# RobotDriverSCH.net
KiCad netlist of a schematic drawn in Altium Designer
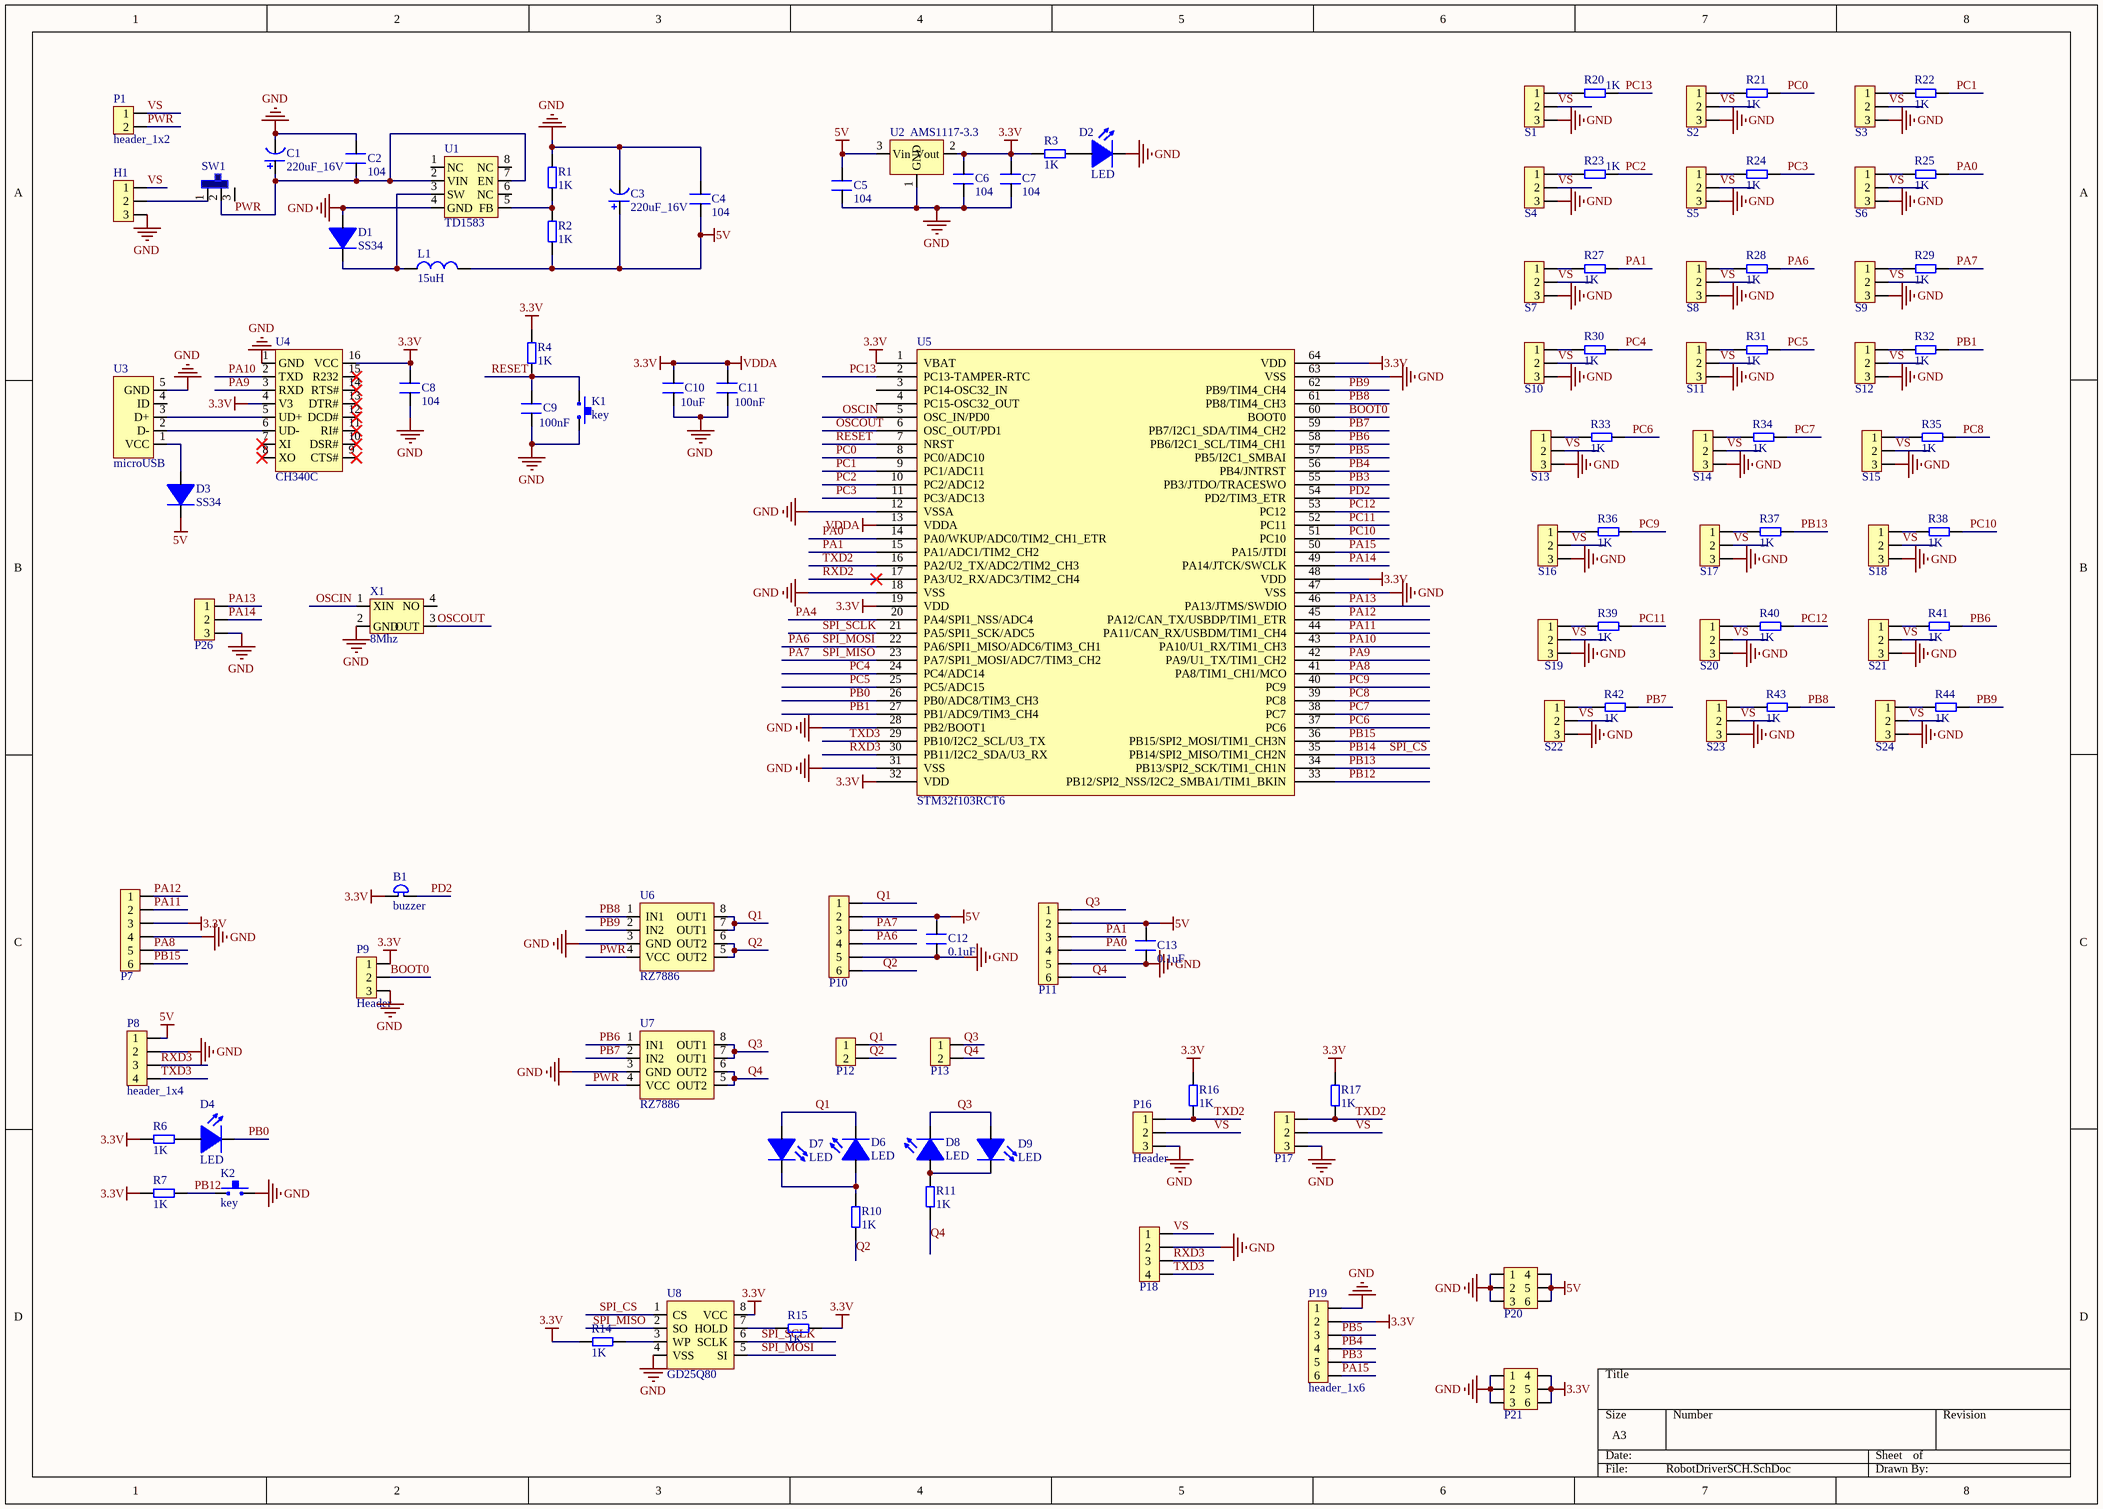
[diagram p0: RobotDriverSCH.SchDoc]

(export (version "E")
  (design (tool "Eeschema 10.0.6"))
  (components
    (comp (ref "B1")
      (value "buzzer")
      (footprint "BEEP 5x9x5.5")
      (libsource (lib "RobotDriverSCHLib") (part "buzzer"))
    )
    (comp (ref "C1")
      (value "220uF_16V")
      (footprint "CM D(6.3*7.7)")
      (libsource (lib "RobotDriverSCHLib") (part "CAP_220uF_16V"))
    )
    (comp (ref "C2") (value "104") (footprint "C 0603") (libsource (lib "RobotDriverSCHLib") (part "C_0603")))
    (comp (ref "C3")
      (value "220uF_16V")
      (footprint "CM D(6.3*7.7)")
      (libsource (lib "RobotDriverSCHLib") (part "CAP_220uF_16V"))
    )
    (comp (ref "C4") (value "104") (footprint "C 0603") (libsource (lib "RobotDriverSCHLib") (part "C_0603")))
    (comp (ref "C5") (value "104") (footprint "C 0603") (libsource (lib "RobotDriverSCHLib") (part "C_0603")))
    (comp (ref "C6") (value "104") (footprint "C 0603") (libsource (lib "RobotDriverSCHLib") (part "C_0603")))
    (comp (ref "C7") (value "104") (footprint "C 0603") (libsource (lib "RobotDriverSCHLib") (part "C_0603")))
    (comp (ref "C8") (value "104") (footprint "C 0603") (libsource (lib "RobotDriverSCHLib") (part "C_0603")))
    (comp (ref "C9")
      (value "100nF")
      (footprint "C 0603")
      (libsource (lib "RobotDriverSCHLib") (part "C_0603"))
    )
    (comp (ref "C10")
      (value "10uF")
      (footprint "C 0603")
      (libsource (lib "RobotDriverSCHLib") (part "C_0603"))
    )
    (comp (ref "C11")
      (value "100nF")
      (footprint "C 0603")
      (libsource (lib "RobotDriverSCHLib") (part "C_0603"))
    )
    (comp (ref "C12")
      (value "0.1uF")
      (footprint "C 0603")
      (libsource (lib "RobotDriverSCHLib") (part "C_0603"))
    )
    (comp (ref "C13")
      (value "0.1uF")
      (footprint "C 0603")
      (libsource (lib "RobotDriverSCHLib") (part "C_0603"))
    )
    (comp (ref "D1") (value "SS34") (footprint "SMA") (libsource (lib "RobotDriverSCHLib") (part "SS34")))
    (comp (ref "D2") (value "LED") (footprint "LED 0603R") (libsource (lib "RobotDriverSCHLib") (part "LED")))
    (comp (ref "D3") (value "SS34") (footprint "SMA") (libsource (lib "RobotDriverSCHLib") (part "SS34")))
    (comp (ref "D4") (value "LED") (footprint "LED 0603R") (libsource (lib "RobotDriverSCHLib") (part "LED")))
    (comp (ref "D6") (value "LED") (footprint "LED 0603R") (libsource (lib "RobotDriverSCHLib") (part "LED")))
    (comp (ref "D7") (value "LED") (footprint "LED 0603R") (libsource (lib "RobotDriverSCHLib") (part "LED")))
    (comp (ref "D8") (value "LED") (footprint "LED 0603R") (libsource (lib "RobotDriverSCHLib") (part "LED")))
    (comp (ref "D9") (value "LED") (footprint "LED 0603R") (libsource (lib "RobotDriverSCHLib") (part "LED")))
    (comp (ref "H1")
      (value "header")
      (footprint "KF128-3.81-3P")
      (libsource (lib "RobotDriverSCHLib") (part "PowerHead"))
    )
    (comp (ref "K1") (value "key") (footprint "TSW SMD-3*6*4.3") (libsource (lib "") (part "key_1")))
    (comp (ref "K2")
      (value "key")
      (footprint "TSW SMD-3*6*4.3")
      (libsource (lib "RobotDriverSCHLib") (part "key"))
    )
    (comp (ref "L1")
      (value "15uH")
      (footprint "NR6045")
      (libsource (lib "RobotDriverSCHLib") (part "L_6045"))
    )
    (comp (ref "P1")
      (value "header_1x2")
      (footprint "HDR2.54-LI-2P")
      (libsource (lib "RobotDriverSCHLib") (part "header_1x2"))
    )
    (comp (ref "P7")
      (value "PS2无线手柄")
      (footprint "XH2.54-LI-6P")
      (libsource (lib "RobotDriverSCHLib") (part "xh2.54_1x6"))
    )
    (comp (ref "P8")
      (value "header_1x4")
      (footprint "HDR2.54-LI-4P")
      (libsource (lib "RobotDriverSCHLib") (part "header_1x4"))
    )
    (comp (ref "P9")
      (value "Header")
      (footprint "HDR2.54-LI-3P")
      (libsource (lib "RobotDriverSCHLib") (part "header_1x3"))
    )
    (comp (ref "P10")
      (value "XH2.54W_1X6")
      (footprint "XH2.54-WI-6P")
      (libsource (lib "RobotDriverSCHLib") (part "XH2.54W_1X6"))
    )
    (comp (ref "P11")
      (value "XH2.54W_1X6")
      (footprint "XH2.54-WI-6P")
      (libsource (lib "RobotDriverSCHLib") (part "XH2.54W_1X6"))
    )
    (comp (ref "P12")
      (value "KF2.54_1x2")
      (footprint "KF2EDGK-2.54-WI-2P")
      (libsource (lib "RobotDriverSCHLib") (part "KF2.54_1x2"))
    )
    (comp (ref "P13")
      (value "KF2.54_1x2")
      (footprint "KF2EDGK-2.54-WI-2P")
      (libsource (lib "RobotDriverSCHLib") (part "KF2.54_1x2"))
    )
    (comp (ref "P16")
      (value "Header")
      (footprint "XH2.54-WI-3P")
      (libsource (lib "RobotDriverSCHLib") (part "header_1x3"))
    )
    (comp (ref "P17")
      (value "Header")
      (footprint "XH2.54-WI-3P")
      (libsource (lib "RobotDriverSCHLib") (part "header_1x3"))
    )
    (comp (ref "P18")
      (value "header_1x4")
      (footprint "XH2.54-WI-4P")
      (libsource (lib "RobotDriverSCHLib") (part "header_1x4"))
    )
    (comp (ref "P19")
      (value "header_1x6")
      (footprint "HDR2.54-M-LI-6P")
      (libsource (lib "RobotDriverSCHLib") (part "header_1x6"))
    )
    (comp (ref "P20")
      (value "Header2x3")
      (footprint "HDR2.54-LI-2x3P")
      (libsource (lib "RobotDriverSCHLib") (part "Header2x3"))
    )
    (comp (ref "P21")
      (value "Header2x3")
      (footprint "HDR2.54-LI-2x3P")
      (libsource (lib "RobotDriverSCHLib") (part "Header2x3"))
    )
    (comp (ref "P26")
      (value "Head_1x3")
      (footprint "HDR2.54-LI-3P")
      (libsource (lib "RobotDriverSCHLib") (part "Head_1x3"))
    )
    (comp (ref "R1") (value "1K") (footprint "0603R") (libsource (lib "RobotDriverSCHLib") (part "R_0603")))
    (comp (ref "R2") (value "1K") (footprint "0603R") (libsource (lib "RobotDriverSCHLib") (part "R_0603")))
    (comp (ref "R3") (value "1K") (footprint "0603R") (libsource (lib "RobotDriverSCHLib") (part "R_0603")))
    (comp (ref "R4") (value "1K") (footprint "0603R") (libsource (lib "RobotDriverSCHLib") (part "R_0603")))
    (comp (ref "R6") (value "1K") (footprint "0603R") (libsource (lib "RobotDriverSCHLib") (part "R_0603")))
    (comp (ref "R7") (value "1K") (footprint "0603R") (libsource (lib "RobotDriverSCHLib") (part "R_0603")))
    (comp (ref "R10") (value "1K") (footprint "0603R") (libsource (lib "RobotDriverSCHLib") (part "R_0603")))
    (comp (ref "R11") (value "1K") (footprint "0603R") (libsource (lib "RobotDriverSCHLib") (part "R_0603")))
    (comp (ref "R14") (value "1K") (footprint "0603R") (libsource (lib "RobotDriverSCHLib") (part "R_0603")))
    (comp (ref "R15") (value "1K") (footprint "0603R") (libsource (lib "RobotDriverSCHLib") (part "R_0603")))
    (comp (ref "R16") (value "1K") (footprint "0603R") (libsource (lib "RobotDriverSCHLib") (part "R_0603")))
    (comp (ref "R17") (value "1K") (footprint "0603R") (libsource (lib "RobotDriverSCHLib") (part "R_0603")))
    (comp (ref "R20") (value "1K") (footprint "0603R") (libsource (lib "RobotDriverSCHLib") (part "R_0603")))
    (comp (ref "R21") (value "1K") (footprint "0603R") (libsource (lib "RobotDriverSCHLib") (part "R_0603")))
    (comp (ref "R22") (value "1K") (footprint "0603R") (libsource (lib "RobotDriverSCHLib") (part "R_0603")))
    (comp (ref "R23") (value "1K") (footprint "0603R") (libsource (lib "RobotDriverSCHLib") (part "R_0603")))
    (comp (ref "R24") (value "1K") (footprint "0603R") (libsource (lib "RobotDriverSCHLib") (part "R_0603")))
    (comp (ref "R25") (value "1K") (footprint "0603R") (libsource (lib "RobotDriverSCHLib") (part "R_0603")))
    (comp (ref "R27") (value "1K") (footprint "0603R") (libsource (lib "RobotDriverSCHLib") (part "R_0603")))
    (comp (ref "R28") (value "1K") (footprint "0603R") (libsource (lib "RobotDriverSCHLib") (part "R_0603")))
    (comp (ref "R29") (value "1K") (footprint "0603R") (libsource (lib "RobotDriverSCHLib") (part "R_0603")))
    (comp (ref "R30") (value "1K") (footprint "0603R") (libsource (lib "RobotDriverSCHLib") (part "R_0603")))
    (comp (ref "R31") (value "1K") (footprint "0603R") (libsource (lib "RobotDriverSCHLib") (part "R_0603")))
    (comp (ref "R32") (value "1K") (footprint "0603R") (libsource (lib "RobotDriverSCHLib") (part "R_0603")))
    (comp (ref "R33") (value "1K") (footprint "0603R") (libsource (lib "RobotDriverSCHLib") (part "R_0603")))
    (comp (ref "R34") (value "1K") (footprint "0603R") (libsource (lib "RobotDriverSCHLib") (part "R_0603")))
    (comp (ref "R35") (value "1K") (footprint "0603R") (libsource (lib "RobotDriverSCHLib") (part "R_0603")))
    (comp (ref "R36") (value "1K") (footprint "0603R") (libsource (lib "RobotDriverSCHLib") (part "R_0603")))
    (comp (ref "R37") (value "1K") (footprint "0603R") (libsource (lib "RobotDriverSCHLib") (part "R_0603")))
    (comp (ref "R38") (value "1K") (footprint "0603R") (libsource (lib "RobotDriverSCHLib") (part "R_0603")))
    (comp (ref "R39") (value "1K") (footprint "0603R") (libsource (lib "RobotDriverSCHLib") (part "R_0603")))
    (comp (ref "R40") (value "1K") (footprint "0603R") (libsource (lib "RobotDriverSCHLib") (part "R_0603")))
    (comp (ref "R41") (value "1K") (footprint "0603R") (libsource (lib "RobotDriverSCHLib") (part "R_0603")))
    (comp (ref "R42") (value "1K") (footprint "0603R") (libsource (lib "RobotDriverSCHLib") (part "R_0603")))
    (comp (ref "R43") (value "1K") (footprint "0603R") (libsource (lib "RobotDriverSCHLib") (part "R_0603")))
    (comp (ref "R44") (value "1K") (footprint "0603R") (libsource (lib "RobotDriverSCHLib") (part "R_0603")))
    (comp (ref "S1")
      (value "Header")
      (footprint "HDR2.54-LI-3P")
      (libsource (lib "RobotDriverSCHLib") (part "header_1x3"))
    )
    (comp (ref "S2")
      (value "Header")
      (footprint "HDR2.54-LI-3P")
      (libsource (lib "RobotDriverSCHLib") (part "header_1x3"))
    )
    (comp (ref "S3")
      (value "Header")
      (footprint "HDR2.54-LI-3P")
      (libsource (lib "RobotDriverSCHLib") (part "header_1x3"))
    )
    (comp (ref "S4")
      (value "Header")
      (footprint "HDR2.54-LI-3P")
      (libsource (lib "RobotDriverSCHLib") (part "header_1x3"))
    )
    (comp (ref "S5")
      (value "Header")
      (footprint "HDR2.54-LI-3P")
      (libsource (lib "RobotDriverSCHLib") (part "header_1x3"))
    )
    (comp (ref "S6")
      (value "Header")
      (footprint "HDR2.54-LI-3P")
      (libsource (lib "RobotDriverSCHLib") (part "header_1x3"))
    )
    (comp (ref "S7")
      (value "Header")
      (footprint "HDR2.54-LI-3P")
      (libsource (lib "RobotDriverSCHLib") (part "header_1x3"))
    )
    (comp (ref "S8")
      (value "Header")
      (footprint "HDR2.54-LI-3P")
      (libsource (lib "RobotDriverSCHLib") (part "header_1x3"))
    )
    (comp (ref "S9")
      (value "Header")
      (footprint "HDR2.54-LI-3P")
      (libsource (lib "RobotDriverSCHLib") (part "header_1x3"))
    )
    (comp (ref "S10")
      (value "Header")
      (footprint "HDR2.54-LI-3P")
      (libsource (lib "RobotDriverSCHLib") (part "header_1x3"))
    )
    (comp (ref "S11")
      (value "Header")
      (footprint "HDR2.54-LI-3P")
      (libsource (lib "RobotDriverSCHLib") (part "header_1x3"))
    )
    (comp (ref "S12")
      (value "Header")
      (footprint "HDR2.54-LI-3P")
      (libsource (lib "RobotDriverSCHLib") (part "header_1x3"))
    )
    (comp (ref "S13")
      (value "Header")
      (footprint "HDR2.54-LI-3P")
      (libsource (lib "RobotDriverSCHLib") (part "header_1x3"))
    )
    (comp (ref "S14")
      (value "Header")
      (footprint "HDR2.54-LI-3P")
      (libsource (lib "RobotDriverSCHLib") (part "header_1x3"))
    )
    (comp (ref "S15")
      (value "Header")
      (footprint "HDR2.54-LI-3P")
      (libsource (lib "RobotDriverSCHLib") (part "header_1x3"))
    )
    (comp (ref "S16")
      (value "Header")
      (footprint "HDR2.54-LI-3P")
      (libsource (lib "RobotDriverSCHLib") (part "header_1x3"))
    )
    (comp (ref "S17")
      (value "Header")
      (footprint "HDR2.54-LI-3P")
      (libsource (lib "RobotDriverSCHLib") (part "header_1x3"))
    )
    (comp (ref "S18")
      (value "Header")
      (footprint "HDR2.54-LI-3P")
      (libsource (lib "RobotDriverSCHLib") (part "header_1x3"))
    )
    (comp (ref "S19")
      (value "Header")
      (footprint "HDR2.54-LI-3P")
      (libsource (lib "RobotDriverSCHLib") (part "header_1x3"))
    )
    (comp (ref "S20")
      (value "Header")
      (footprint "HDR2.54-LI-3P")
      (libsource (lib "RobotDriverSCHLib") (part "header_1x3"))
    )
    (comp (ref "S21")
      (value "Header")
      (footprint "HDR2.54-LI-3P")
      (libsource (lib "RobotDriverSCHLib") (part "header_1x3"))
    )
    (comp (ref "S22")
      (value "Header")
      (footprint "HDR2.54-LI-3P")
      (libsource (lib "RobotDriverSCHLib") (part "header_1x3"))
    )
    (comp (ref "S23")
      (value "Header")
      (footprint "HDR2.54-LI-3P")
      (libsource (lib "RobotDriverSCHLib") (part "header_1x3"))
    )
    (comp (ref "S24")
      (value "Header")
      (footprint "HDR2.54-LI-3P")
      (libsource (lib "RobotDriverSCHLib") (part "header_1x3"))
    )
    (comp (ref "SW1")
      (value "Switch")
      (footprint "SS12D10")
      (libsource (lib "RobotDriverSCHLib") (part "SS12D10"))
    )
    (comp (ref "U1")
      (value "TD1583")
      (footprint "SOP8")
      (libsource (lib "RobotDriverSCHLib") (part "TD1583"))
    )
    (comp (ref "U2")
      (value "AMS1117-3.3")
      (footprint "SOT-223")
      (libsource (lib "RobotDriverSCHLib") (part "AMS1117-3.3"))
    )
    (comp (ref "U3")
      (value "microUSB")
      (footprint "USB-MICRO_B")
      (libsource (lib "RobotDriverSCHLib") (part "MicroUSB_B"))
    )
    (comp (ref "U4")
      (value "CH340C")
      (footprint "SOP16")
      (libsource (lib "RobotDriverSCHLib") (part "CH340C"))
    )
    (comp (ref "U5")
      (value "STM32f103RCT6")
      (footprint "LQFP_64")
      (libsource (lib "RobotDriverSCHLib") (part "STM32f103RCT6"))
    )
    (comp (ref "U6")
      (value "RZ7886")
      (footprint "DIP8")
      (libsource (lib "RobotDriverSCHLib") (part "RZ7886"))
    )
    (comp (ref "U7")
      (value "RZ7886")
      (footprint "DIP8")
      (libsource (lib "RobotDriverSCHLib") (part "RZ7886"))
    )
    (comp (ref "U8")
      (value "GD25Q80")
      (footprint "SOP8")
      (libsource (lib "RobotDriverSCHLib") (part "flash"))
    )
    (comp (ref "X1")
      (value "8Mhz")
      (footprint "OSC 3225-4P")
      (libsource (lib "RobotDriverSCHLib") (part "XTAL"))
    )
  )
  (nets
    (net (code "1") (name "/BOOT0") (class "Default")
      (node (ref "P9") (pin "2") (pinfunction "2_2") (pintype "passive"))
      (node (ref "U5") (pin "60") (pinfunction "BOOT0_60") (pintype "passive"))
    )
    (net (code "2") (name "/OSCIN") (class "Default")
      (node (ref "U5") (pin "5") (pinfunction "OSC_IN/PD0_5") (pintype "passive"))
      (node (ref "X1") (pin "1") (pinfunction "XIN_1") (pintype "passive"))
    )
    (net (code "3") (name "/OSCOUT") (class "Default")
      (node (ref "U5") (pin "6") (pinfunction "OSC_OUT/PD1_6") (pintype "passive"))
      (node (ref "X1") (pin "3") (pinfunction "OUT_3") (pintype "passive"))
    )
    (net (code "4") (name "/PA0") (class "Default")
      (node (ref "P11") (pin "4") (pinfunction "4_4") (pintype "passive"))
      (node (ref "R25") (pin "2") (pinfunction "2_2") (pintype "passive"))
      (node (ref "U5") (pin "14") (pinfunction "PA0/WKUP/ADC0/TIM2_CH1_ETR_14") (pintype "passive"))
    )
    (net (code "5") (name "/PA1") (class "Default")
      (node (ref "P11") (pin "3") (pinfunction "3_3") (pintype "passive"))
      (node (ref "R27") (pin "2") (pinfunction "2_2") (pintype "passive"))
      (node (ref "U5") (pin "15") (pinfunction "PA1/ADC1/TIM2_CH2_15") (pintype "passive"))
    )
    (net (code "6") (name "/PA4") (class "Default")
      (node (ref "U5") (pin "20") (pinfunction "PA4/SPI1_NSS/ADC4_20") (pintype "passive"))
    )
    (net (code "7") (name "/PA6") (class "Default")
      (node (ref "P10") (pin "4") (pinfunction "4_4") (pintype "passive"))
      (node (ref "R28") (pin "2") (pinfunction "2_2") (pintype "passive"))
      (node (ref "U5") (pin "22") (pinfunction "PA6/SPI1_MISO/ADC6/TIM3_CH1_22") (pintype "passive"))
      (node (ref "U8") (pin "5") (pinfunction "SI_5") (pintype "passive"))
    )
    (net (code "8") (name "/PA7") (class "Default")
      (node (ref "P10") (pin "3") (pinfunction "3_3") (pintype "passive"))
      (node (ref "R29") (pin "2") (pinfunction "2_2") (pintype "passive"))
      (node (ref "U5") (pin "23") (pinfunction "PA7/SPI1_MOSI/ADC7/TIM3_CH2_23") (pintype "passive"))
      (node (ref "U8") (pin "2") (pinfunction "SO_2") (pintype "passive"))
    )
    (net (code "9") (name "/PA8") (class "Default")
      (node (ref "P7") (pin "5") (pinfunction "5_5") (pintype "passive"))
      (node (ref "U5") (pin "41") (pinfunction "PA8/TIM1_CH1/MCO_41") (pintype "passive"))
    )
    (net (code "10") (name "/PA9") (class "Default")
      (node (ref "U4") (pin "3") (pinfunction "RXD_3") (pintype "passive"))
      (node (ref "U5") (pin "42") (pinfunction "PA9/U1_TX/TIM1_CH2_42") (pintype "passive"))
    )
    (net (code "11") (name "/PA10") (class "Default")
      (node (ref "U4") (pin "2") (pinfunction "TXD_2") (pintype "passive"))
      (node (ref "U5") (pin "43") (pinfunction "PA10/U1_RX/TIM1_CH3_43") (pintype "passive"))
    )
    (net (code "12") (name "/PA11") (class "Default")
      (node (ref "P7") (pin "2") (pinfunction "2_2") (pintype "passive"))
      (node (ref "U5") (pin "44") (pinfunction "PA11/CAN_RX/USBDM/TIM1_CH4_44") (pintype "passive"))
    )
    (net (code "13") (name "/PA12") (class "Default")
      (node (ref "P7") (pin "1") (pinfunction "1_1") (pintype "passive"))
      (node (ref "U5") (pin "45") (pinfunction "PA12/CAN_TX/USBDP/TIM1_ETR_45") (pintype "passive"))
    )
    (net (code "14") (name "/PA13") (class "Default")
      (node (ref "P26") (pin "1") (pinfunction "1_1") (pintype "passive"))
      (node (ref "U5") (pin "46") (pinfunction "PA13/JTMS/SWDIO_46") (pintype "passive"))
    )
    (net (code "15") (name "/PA14") (class "Default")
      (node (ref "P26") (pin "2") (pinfunction "2_2") (pintype "passive"))
      (node (ref "U5") (pin "49") (pinfunction "PA14/JTCK/SWCLK_49") (pintype "passive"))
    )
    (net (code "16") (name "/PA15") (class "Default")
      (node (ref "P19") (pin "6") (pinfunction "6_6") (pintype "passive"))
      (node (ref "U5") (pin "50") (pinfunction "PA15/JTDI_50") (pintype "passive"))
    )
    (net (code "17") (name "/PB0") (class "Default")
      (node (ref "D4") (pin "2") (pinfunction "2_2") (pintype "passive"))
      (node (ref "U5") (pin "26") (pinfunction "PB0/ADC8/TIM3_CH3_26") (pintype "passive"))
    )
    (net (code "18") (name "/PB1") (class "Default")
      (node (ref "R32") (pin "2") (pinfunction "2_2") (pintype "passive"))
      (node (ref "U5") (pin "27") (pinfunction "PB1/ADC9/TIM3_CH4_27") (pintype "passive"))
    )
    (net (code "19") (name "/PB3") (class "Default")
      (node (ref "P19") (pin "5") (pinfunction "5_5") (pintype "passive"))
      (node (ref "U5") (pin "55") (pinfunction "PB3/JTDO/TRACESWO_55") (pintype "passive"))
    )
    (net (code "20") (name "/PB4") (class "Default")
      (node (ref "P19") (pin "4") (pinfunction "4_4") (pintype "passive"))
      (node (ref "U5") (pin "56") (pinfunction "PB4/JNTRST_56") (pintype "passive"))
    )
    (net (code "21") (name "/PB5") (class "Default")
      (node (ref "P19") (pin "3") (pinfunction "3_3") (pintype "passive"))
      (node (ref "U5") (pin "57") (pinfunction "PB5/I2C1_SMBAI_57") (pintype "passive"))
    )
    (net (code "22") (name "/PB6") (class "Default")
      (node (ref "R41") (pin "2") (pinfunction "2_2") (pintype "passive"))
      (node (ref "U5") (pin "58") (pinfunction "PB6/I2C1_SCL/TIM4_CH1_58") (pintype "passive"))
      (node (ref "U7") (pin "1") (pinfunction "IN1_1") (pintype "passive"))
    )
    (net (code "23") (name "/PB7") (class "Default")
      (node (ref "R42") (pin "2") (pinfunction "2_2") (pintype "passive"))
      (node (ref "U5") (pin "59") (pinfunction "PB7/I2C1_SDA/TIM4_CH2_59") (pintype "passive"))
      (node (ref "U7") (pin "2") (pinfunction "IN2_2") (pintype "passive"))
    )
    (net (code "24") (name "/PB8") (class "Default")
      (node (ref "R43") (pin "2") (pinfunction "2_2") (pintype "passive"))
      (node (ref "U5") (pin "61") (pinfunction "PB8/TIM4_CH3_61") (pintype "passive"))
      (node (ref "U6") (pin "1") (pinfunction "IN1_1") (pintype "passive"))
    )
    (net (code "25") (name "/PB9") (class "Default")
      (node (ref "R44") (pin "2") (pinfunction "2_2") (pintype "passive"))
      (node (ref "U5") (pin "62") (pinfunction "PB9/TIM4_CH4_62") (pintype "passive"))
      (node (ref "U6") (pin "2") (pinfunction "IN2_2") (pintype "passive"))
    )
    (net (code "26") (name "/PB12") (class "Default")
      (node (ref "K2") (pin "1") (pinfunction "1_1") (pintype "passive"))
      (node (ref "R7") (pin "2") (pinfunction "2_2") (pintype "passive"))
      (node (ref "U5") (pin "33") (pinfunction "PB12/SPI2_NSS/I2C2_SMBA1/TIM1_BKIN_33") (pintype "passive"))
    )
    (net (code "27") (name "/PB13") (class "Default")
      (node (ref "R37") (pin "2") (pinfunction "2_2") (pintype "passive"))
      (node (ref "U5") (pin "34") (pinfunction "PB13/SPI2_SCK/TIM1_CH1N_34") (pintype "passive"))
    )
    (net (code "28") (name "/PB14") (class "Default")
      (node (ref "U5") (pin "35") (pinfunction "PB14/SPI2_MISO/TIM1_CH2N_35") (pintype "passive"))
      (node (ref "U8") (pin "1") (pinfunction "CS_1") (pintype "passive"))
    )
    (net (code "29") (name "/PB15") (class "Default")
      (node (ref "P7") (pin "6") (pinfunction "6_6") (pintype "passive"))
      (node (ref "U5") (pin "36") (pinfunction "PB15/SPI2_MOSI/TIM1_CH3N_36") (pintype "passive"))
    )
    (net (code "30") (name "/PC0") (class "Default")
      (node (ref "R21") (pin "2") (pinfunction "2_2") (pintype "passive"))
      (node (ref "U5") (pin "8") (pinfunction "PC0/ADC10_8") (pintype "passive"))
    )
    (net (code "31") (name "/PC1") (class "Default")
      (node (ref "R22") (pin "2") (pinfunction "2_2") (pintype "passive"))
      (node (ref "U5") (pin "9") (pinfunction "PC1/ADC11_9") (pintype "passive"))
    )
    (net (code "32") (name "/PC2") (class "Default")
      (node (ref "R23") (pin "2") (pinfunction "2_2") (pintype "passive"))
      (node (ref "U5") (pin "10") (pinfunction "PC2/ADC12_10") (pintype "passive"))
    )
    (net (code "33") (name "/PC3") (class "Default")
      (node (ref "R24") (pin "2") (pinfunction "2_2") (pintype "passive"))
      (node (ref "U5") (pin "11") (pinfunction "PC3/ADC13_11") (pintype "passive"))
    )
    (net (code "34") (name "/PC4") (class "Default")
      (node (ref "R30") (pin "2") (pinfunction "2_2") (pintype "passive"))
      (node (ref "U5") (pin "24") (pinfunction "PC4/ADC14_24") (pintype "passive"))
    )
    (net (code "35") (name "/PC5") (class "Default")
      (node (ref "R31") (pin "2") (pinfunction "2_2") (pintype "passive"))
      (node (ref "U5") (pin "25") (pinfunction "PC5/ADC15_25") (pintype "passive"))
    )
    (net (code "36") (name "/PC6") (class "Default")
      (node (ref "R33") (pin "2") (pinfunction "2_2") (pintype "passive"))
      (node (ref "U5") (pin "37") (pinfunction "PC6_37") (pintype "passive"))
    )
    (net (code "37") (name "/PC7") (class "Default")
      (node (ref "R34") (pin "2") (pinfunction "2_2") (pintype "passive"))
      (node (ref "U5") (pin "38") (pinfunction "PC7_38") (pintype "passive"))
    )
    (net (code "38") (name "/PC8") (class "Default")
      (node (ref "R35") (pin "2") (pinfunction "2_2") (pintype "passive"))
      (node (ref "U5") (pin "39") (pinfunction "PC8_39") (pintype "passive"))
    )
    (net (code "39") (name "/PC9") (class "Default")
      (node (ref "R36") (pin "2") (pinfunction "2_2") (pintype "passive"))
      (node (ref "U5") (pin "40") (pinfunction "PC9_40") (pintype "passive"))
    )
    (net (code "40") (name "/PC10") (class "Default")
      (node (ref "R38") (pin "2") (pinfunction "2_2") (pintype "passive"))
      (node (ref "U5") (pin "51") (pinfunction "PC10_51") (pintype "passive"))
    )
    (net (code "41") (name "/PC11") (class "Default")
      (node (ref "R39") (pin "2") (pinfunction "2_2") (pintype "passive"))
      (node (ref "U5") (pin "52") (pinfunction "PC11_52") (pintype "passive"))
    )
    (net (code "42") (name "/PC12") (class "Default")
      (node (ref "R40") (pin "2") (pinfunction "2_2") (pintype "passive"))
      (node (ref "U5") (pin "53") (pinfunction "PC12_53") (pintype "passive"))
    )
    (net (code "43") (name "/PC13") (class "Default")
      (node (ref "R20") (pin "2") (pinfunction "2_2") (pintype "passive"))
      (node (ref "U5") (pin "2") (pinfunction "PC13-TAMPER-RTC_2") (pintype "passive"))
    )
    (net (code "44") (name "/PD2") (class "Default")
      (node (ref "B1") (pin "2") (pinfunction "2_2") (pintype "passive"))
      (node (ref "U5") (pin "54") (pinfunction "PD2/TIM3_ETR_54") (pintype "passive"))
    )
    (net (code "45") (name "/PWR") (class "Default")
      (node (ref "C1") (pin "1") (pinfunction "1_1") (pintype "passive"))
      (node (ref "C2") (pin "2") (pinfunction "2_2") (pintype "passive"))
      (node (ref "P1") (pin "2") (pinfunction "2_2") (pintype "passive"))
      (node (ref "SW1") (pin "2") (pinfunction "2_2") (pintype "passive"))
      (node (ref "U1") (pin "2") (pinfunction "VIN_2") (pintype "passive"))
      (node (ref "U1") (pin "7") (pinfunction "EN_7") (pintype "passive"))
      (node (ref "U6") (pin "4") (pinfunction "VCC_4") (pintype "passive"))
      (node (ref "U7") (pin "4") (pinfunction "VCC_4") (pintype "passive"))
    )
    (net (code "46") (name "/Q1") (class "Default")
      (node (ref "D6") (pin "2") (pinfunction "2_2") (pintype "passive"))
      (node (ref "D7") (pin "1") (pinfunction "1_1") (pintype "passive"))
      (node (ref "P10") (pin "1") (pinfunction "1_1") (pintype "passive"))
      (node (ref "P12") (pin "1") (pinfunction "1_1") (pintype "passive"))
      (node (ref "U6") (pin "7") (pinfunction "OUT1_7") (pintype "passive"))
      (node (ref "U6") (pin "8") (pinfunction "OUT1_8") (pintype "passive"))
    )
    (net (code "47") (name "/Q2") (class "Default")
      (node (ref "P10") (pin "6") (pinfunction "6_6") (pintype "passive"))
      (node (ref "P12") (pin "2") (pinfunction "2_2") (pintype "passive"))
      (node (ref "R10") (pin "1") (pinfunction "1_1") (pintype "passive"))
      (node (ref "U6") (pin "5") (pinfunction "OUT2_5") (pintype "passive"))
      (node (ref "U6") (pin "6") (pinfunction "OUT2_6") (pintype "passive"))
    )
    (net (code "48") (name "/Q3") (class "Default")
      (node (ref "D8") (pin "2") (pinfunction "2_2") (pintype "passive"))
      (node (ref "D9") (pin "1") (pinfunction "1_1") (pintype "passive"))
      (node (ref "P11") (pin "1") (pinfunction "1_1") (pintype "passive"))
      (node (ref "P13") (pin "1") (pinfunction "1_1") (pintype "passive"))
      (node (ref "U7") (pin "7") (pinfunction "OUT1_7") (pintype "passive"))
      (node (ref "U7") (pin "8") (pinfunction "OUT1_8") (pintype "passive"))
    )
    (net (code "49") (name "/Q4") (class "Default")
      (node (ref "P11") (pin "6") (pinfunction "6_6") (pintype "passive"))
      (node (ref "P13") (pin "2") (pinfunction "2_2") (pintype "passive"))
      (node (ref "R11") (pin "1") (pinfunction "1_1") (pintype "passive"))
      (node (ref "U7") (pin "5") (pinfunction "OUT2_5") (pintype "passive"))
      (node (ref "U7") (pin "6") (pinfunction "OUT2_6") (pintype "passive"))
    )
    (net (code "50") (name "/RESET") (class "Default")
      (node (ref "C9") (pin "1") (pinfunction "1_1") (pintype "passive"))
      (node (ref "K1") (pin "1") (pinfunction "1_1") (pintype "passive"))
      (node (ref "R4") (pin "1") (pinfunction "1_1") (pintype "passive"))
      (node (ref "U5") (pin "7") (pinfunction "NRST_7") (pintype "passive"))
    )
    (net (code "51") (name "/RXD2") (class "Default")
      (node (ref "U5") (pin "17") (pinfunction "PA3/U2_RX/ADC3/TIM2_CH4_17") (pintype "passive+no_connect"))
    )
    (net (code "52") (name "/RXD3") (class "Default")
      (node (ref "P18") (pin "3") (pinfunction "3_3") (pintype "passive"))
      (node (ref "P8") (pin "3") (pinfunction "3_3") (pintype "passive"))
      (node (ref "U5") (pin "30") (pinfunction "PB11/I2C2_SDA/U3_RX_30") (pintype "passive"))
    )
    (net (code "53") (name "/SPI_SCLK") (class "Default")
      (node (ref "U5") (pin "21") (pinfunction "PA5/SPI1_SCK/ADC5_21") (pintype "passive"))
      (node (ref "U8") (pin "6") (pinfunction "SCLK_6") (pintype "passive"))
    )
    (net (code "54") (name "/TXD2") (class "Default")
      (node (ref "P16") (pin "1") (pinfunction "1_1") (pintype "passive"))
      (node (ref "P17") (pin "1") (pinfunction "1_1") (pintype "passive"))
      (node (ref "R16") (pin "1") (pinfunction "1_1") (pintype "passive"))
      (node (ref "R17") (pin "1") (pinfunction "1_1") (pintype "passive"))
      (node (ref "U5") (pin "16") (pinfunction "PA2/U2_TX/ADC2/TIM2_CH3_16") (pintype "passive"))
    )
    (net (code "55") (name "/TXD3") (class "Default")
      (node (ref "P18") (pin "4") (pinfunction "4_4") (pintype "passive"))
      (node (ref "P8") (pin "4") (pinfunction "4_4") (pintype "passive"))
      (node (ref "U5") (pin "29") (pinfunction "PB10/I2C2_SCL/U3_TX_29") (pintype "passive"))
    )
    (net (code "56") (name "/VS") (class "Default")
      (node (ref "H1") (pin "1") (pinfunction "1_1") (pintype "passive"))
      (node (ref "P1") (pin "1") (pinfunction "1_1") (pintype "passive"))
      (node (ref "P16") (pin "2") (pinfunction "2_2") (pintype "passive"))
      (node (ref "P17") (pin "2") (pinfunction "2_2") (pintype "passive"))
      (node (ref "P18") (pin "1") (pinfunction "1_1") (pintype "passive"))
      (node (ref "S1") (pin "2") (pinfunction "2_2") (pintype "passive"))
      (node (ref "S10") (pin "2") (pinfunction "2_2") (pintype "passive"))
      (node (ref "S11") (pin "2") (pinfunction "2_2") (pintype "passive"))
      (node (ref "S12") (pin "2") (pinfunction "2_2") (pintype "passive"))
      (node (ref "S13") (pin "2") (pinfunction "2_2") (pintype "passive"))
      (node (ref "S14") (pin "2") (pinfunction "2_2") (pintype "passive"))
      (node (ref "S15") (pin "2") (pinfunction "2_2") (pintype "passive"))
      (node (ref "S16") (pin "2") (pinfunction "2_2") (pintype "passive"))
      (node (ref "S17") (pin "2") (pinfunction "2_2") (pintype "passive"))
      (node (ref "S18") (pin "2") (pinfunction "2_2") (pintype "passive"))
      (node (ref "S19") (pin "2") (pinfunction "2_2") (pintype "passive"))
      (node (ref "S2") (pin "2") (pinfunction "2_2") (pintype "passive"))
      (node (ref "S20") (pin "2") (pinfunction "2_2") (pintype "passive"))
      (node (ref "S21") (pin "2") (pinfunction "2_2") (pintype "passive"))
      (node (ref "S22") (pin "2") (pinfunction "2_2") (pintype "passive"))
      (node (ref "S23") (pin "2") (pinfunction "2_2") (pintype "passive"))
      (node (ref "S24") (pin "2") (pinfunction "2_2") (pintype "passive"))
      (node (ref "S3") (pin "2") (pinfunction "2_2") (pintype "passive"))
      (node (ref "S4") (pin "2") (pinfunction "2_2") (pintype "passive"))
      (node (ref "S5") (pin "2") (pinfunction "2_2") (pintype "passive"))
      (node (ref "S6") (pin "2") (pinfunction "2_2") (pintype "passive"))
      (node (ref "S7") (pin "2") (pinfunction "2_2") (pintype "passive"))
      (node (ref "S8") (pin "2") (pinfunction "2_2") (pintype "passive"))
      (node (ref "S9") (pin "2") (pinfunction "2_2") (pintype "passive"))
    )
    (net (code "57") (name "3.3V") (class "Default")
      (node (ref "B1") (pin "1") (pinfunction "1_1") (pintype "passive"))
      (node (ref "C10") (pin "1") (pinfunction "1_1") (pintype "passive"))
      (node (ref "C11") (pin "1") (pinfunction "1_1") (pintype "passive"))
      (node (ref "C6") (pin "1") (pinfunction "1_1") (pintype "passive"))
      (node (ref "C7") (pin "1") (pinfunction "1_1") (pintype "passive"))
      (node (ref "C8") (pin "1") (pinfunction "1_1") (pintype "passive"))
      (node (ref "P19") (pin "2") (pinfunction "2_2") (pintype "passive"))
      (node (ref "P21") (pin "4") (pinfunction "4_4") (pintype "passive"))
      (node (ref "P21") (pin "5") (pinfunction "5_5") (pintype "passive"))
      (node (ref "P21") (pin "6") (pinfunction "6_6") (pintype "passive"))
      (node (ref "P7") (pin "3") (pinfunction "3_3") (pintype "passive"))
      (node (ref "P9") (pin "1") (pinfunction "1_1") (pintype "passive"))
      (node (ref "R14") (pin "1") (pinfunction "1_1") (pintype "passive"))
      (node (ref "R15") (pin "2") (pinfunction "2_2") (pintype "passive"))
      (node (ref "R16") (pin "2") (pinfunction "2_2") (pintype "passive"))
      (node (ref "R17") (pin "2") (pinfunction "2_2") (pintype "passive"))
      (node (ref "R3") (pin "1") (pinfunction "1_1") (pintype "passive"))
      (node (ref "R4") (pin "2") (pinfunction "2_2") (pintype "passive"))
      (node (ref "R6") (pin "1") (pinfunction "1_1") (pintype "passive"))
      (node (ref "R7") (pin "1") (pinfunction "1_1") (pintype "passive"))
      (node (ref "U2") (pin "2") (pinfunction "Vout_2") (pintype "passive"))
      (node (ref "U4") (pin "16") (pinfunction "VCC_16") (pintype "passive"))
      (node (ref "U4") (pin "4") (pinfunction "V3_4") (pintype "passive"))
      (node (ref "U5") (pin "1") (pinfunction "VBAT_1") (pintype "passive"))
      (node (ref "U5") (pin "13") (pinfunction "VDDA_13") (pintype "passive"))
      (node (ref "U5") (pin "19") (pinfunction "VDD_19") (pintype "passive"))
      (node (ref "U5") (pin "32") (pinfunction "VDD_32") (pintype "passive"))
      (node (ref "U5") (pin "48") (pinfunction "VDD_48") (pintype "passive"))
      (node (ref "U5") (pin "64") (pinfunction "VDD_64") (pintype "passive"))
      (node (ref "U8") (pin "8") (pinfunction "VCC_8") (pintype "passive"))
    )
    (net (code "58") (name "5V") (class "Default")
      (node (ref "C12") (pin "1") (pinfunction "1_1") (pintype "passive"))
      (node (ref "C13") (pin "1") (pinfunction "1_1") (pintype "passive"))
      (node (ref "C3") (pin "1") (pinfunction "1_1") (pintype "passive"))
      (node (ref "C4") (pin "2") (pinfunction "2_2") (pintype "passive"))
      (node (ref "C5") (pin "1") (pinfunction "1_1") (pintype "passive"))
      (node (ref "D3") (pin "2") (pinfunction "2_2") (pintype "passive"))
      (node (ref "L1") (pin "2") (pinfunction "2_2") (pintype "passive"))
      (node (ref "P10") (pin "2") (pinfunction "2_2") (pintype "passive"))
      (node (ref "P11") (pin "2") (pinfunction "2_2") (pintype "passive"))
      (node (ref "P20") (pin "4") (pinfunction "4_4") (pintype "passive"))
      (node (ref "P20") (pin "5") (pinfunction "5_5") (pintype "passive"))
      (node (ref "P20") (pin "6") (pinfunction "6_6") (pintype "passive"))
      (node (ref "P8") (pin "1") (pinfunction "1_1") (pintype "passive"))
      (node (ref "R2") (pin "1") (pinfunction "1_1") (pintype "passive"))
      (node (ref "U2") (pin "3") (pinfunction "Vin_3") (pintype "passive"))
    )
    (net (code "59") (name "GND") (class "Default")
      (node (ref "C1") (pin "2") (pinfunction "2_2") (pintype "passive"))
      (node (ref "C10") (pin "2") (pinfunction "2_2") (pintype "passive"))
      (node (ref "C11") (pin "2") (pinfunction "2_2") (pintype "passive"))
      (node (ref "C12") (pin "2") (pinfunction "2_2") (pintype "passive"))
      (node (ref "C13") (pin "2") (pinfunction "2_2") (pintype "passive"))
      (node (ref "C2") (pin "1") (pinfunction "1_1") (pintype "passive"))
      (node (ref "C3") (pin "2") (pinfunction "2_2") (pintype "passive"))
      (node (ref "C4") (pin "1") (pinfunction "1_1") (pintype "passive"))
      (node (ref "C5") (pin "2") (pinfunction "2_2") (pintype "passive"))
      (node (ref "C6") (pin "2") (pinfunction "2_2") (pintype "passive"))
      (node (ref "C7") (pin "2") (pinfunction "2_2") (pintype "passive"))
      (node (ref "C8") (pin "2") (pinfunction "2_2") (pintype "passive"))
      (node (ref "C9") (pin "2") (pinfunction "2_2") (pintype "passive"))
      (node (ref "D1") (pin "1") (pinfunction "1_1") (pintype "passive"))
      (node (ref "D2") (pin "2") (pinfunction "2_2") (pintype "passive"))
      (node (ref "H1") (pin "3") (pinfunction "3_3") (pintype "passive"))
      (node (ref "K1") (pin "2") (pinfunction "2_2") (pintype "passive"))
      (node (ref "K2") (pin "2") (pinfunction "2_2") (pintype "passive"))
      (node (ref "P10") (pin "5") (pinfunction "5_5") (pintype "passive"))
      (node (ref "P11") (pin "5") (pinfunction "5_5") (pintype "passive"))
      (node (ref "P16") (pin "3") (pinfunction "3_3") (pintype "passive"))
      (node (ref "P17") (pin "3") (pinfunction "3_3") (pintype "passive"))
      (node (ref "P18") (pin "2") (pinfunction "2_2") (pintype "passive"))
      (node (ref "P19") (pin "1") (pinfunction "1_1") (pintype "passive"))
      (node (ref "P20") (pin "1") (pinfunction "1_1") (pintype "passive"))
      (node (ref "P20") (pin "2") (pinfunction "2_2") (pintype "passive"))
      (node (ref "P20") (pin "3") (pinfunction "3_3") (pintype "passive"))
      (node (ref "P21") (pin "1") (pinfunction "1_1") (pintype "passive"))
      (node (ref "P21") (pin "2") (pinfunction "2_2") (pintype "passive"))
      (node (ref "P21") (pin "3") (pinfunction "3_3") (pintype "passive"))
      (node (ref "P26") (pin "3") (pinfunction "3_3") (pintype "passive"))
      (node (ref "P7") (pin "4") (pinfunction "4_4") (pintype "passive"))
      (node (ref "P8") (pin "2") (pinfunction "2_2") (pintype "passive"))
      (node (ref "P9") (pin "3") (pinfunction "3_3") (pintype "passive"))
      (node (ref "R1") (pin "2") (pinfunction "2_2") (pintype "passive"))
      (node (ref "S1") (pin "3") (pinfunction "3_3") (pintype "passive"))
      (node (ref "S10") (pin "3") (pinfunction "3_3") (pintype "passive"))
      (node (ref "S11") (pin "3") (pinfunction "3_3") (pintype "passive"))
      (node (ref "S12") (pin "3") (pinfunction "3_3") (pintype "passive"))
      (node (ref "S13") (pin "3") (pinfunction "3_3") (pintype "passive"))
      (node (ref "S14") (pin "3") (pinfunction "3_3") (pintype "passive"))
      (node (ref "S15") (pin "3") (pinfunction "3_3") (pintype "passive"))
      (node (ref "S16") (pin "3") (pinfunction "3_3") (pintype "passive"))
      (node (ref "S17") (pin "3") (pinfunction "3_3") (pintype "passive"))
      (node (ref "S18") (pin "3") (pinfunction "3_3") (pintype "passive"))
      (node (ref "S19") (pin "3") (pinfunction "3_3") (pintype "passive"))
      (node (ref "S2") (pin "3") (pinfunction "3_3") (pintype "passive"))
      (node (ref "S20") (pin "3") (pinfunction "3_3") (pintype "passive"))
      (node (ref "S21") (pin "3") (pinfunction "3_3") (pintype "passive"))
      (node (ref "S22") (pin "3") (pinfunction "3_3") (pintype "passive"))
      (node (ref "S23") (pin "3") (pinfunction "3_3") (pintype "passive"))
      (node (ref "S24") (pin "3") (pinfunction "3_3") (pintype "passive"))
      (node (ref "S3") (pin "3") (pinfunction "3_3") (pintype "passive"))
      (node (ref "S4") (pin "3") (pinfunction "3_3") (pintype "passive"))
      (node (ref "S5") (pin "3") (pinfunction "3_3") (pintype "passive"))
      (node (ref "S6") (pin "3") (pinfunction "3_3") (pintype "passive"))
      (node (ref "S7") (pin "3") (pinfunction "3_3") (pintype "passive"))
      (node (ref "S8") (pin "3") (pinfunction "3_3") (pintype "passive"))
      (node (ref "S9") (pin "3") (pinfunction "3_3") (pintype "passive"))
      (node (ref "U1") (pin "4") (pinfunction "GND_4") (pintype "passive"))
      (node (ref "U2") (pin "1") (pinfunction "GND_1") (pintype "passive"))
      (node (ref "U3") (pin "5") (pinfunction "GND_5") (pintype "passive"))
      (node (ref "U4") (pin "1") (pinfunction "GND_1") (pintype "passive"))
      (node (ref "U5") (pin "12") (pinfunction "VSSA_12") (pintype "passive"))
      (node (ref "U5") (pin "18") (pinfunction "VSS_18") (pintype "passive"))
      (node (ref "U5") (pin "28") (pinfunction "PB2/BOOT1_28") (pintype "passive"))
      (node (ref "U5") (pin "31") (pinfunction "VSS_31") (pintype "passive"))
      (node (ref "U5") (pin "47") (pinfunction "VSS_47") (pintype "passive"))
      (node (ref "U5") (pin "63") (pinfunction "VSS_63") (pintype "passive"))
      (node (ref "U6") (pin "3") (pinfunction "GND_3") (pintype "passive"))
      (node (ref "U7") (pin "3") (pinfunction "GND_3") (pintype "passive"))
      (node (ref "U8") (pin "4") (pinfunction "VSS_4") (pintype "passive"))
      (node (ref "X1") (pin "2") (pinfunction "GND_2") (pintype "passive"))
    )
    (net (code "60") (name "Net-(D2-Pad1)") (class "Default")
      (node (ref "D2") (pin "1") (pinfunction "1_1") (pintype "passive"))
      (node (ref "R3") (pin "2") (pinfunction "2_2") (pintype "passive"))
    )
    (net (code "61") (name "Net-(D4-Pad1)") (class "Default")
      (node (ref "D4") (pin "1") (pinfunction "1_1") (pintype "passive"))
      (node (ref "R6") (pin "2") (pinfunction "2_2") (pintype "passive"))
    )
    (net (code "62") (name "Net-(D6-Pad1)") (class "Default")
      (node (ref "D6") (pin "1") (pinfunction "1_1") (pintype "passive"))
      (node (ref "D7") (pin "2") (pinfunction "2_2") (pintype "passive"))
      (node (ref "R10") (pin "2") (pinfunction "2_2") (pintype "passive"))
    )
    (net (code "63") (name "Net-(D8-Pad1)") (class "Default")
      (node (ref "D8") (pin "1") (pinfunction "1_1") (pintype "passive"))
      (node (ref "D9") (pin "2") (pinfunction "2_2") (pintype "passive"))
      (node (ref "R11") (pin "2") (pinfunction "2_2") (pintype "passive"))
    )
    (net (code "64") (name "Net-(H1-Pad2)") (class "Default")
      (node (ref "H1") (pin "2") (pinfunction "2_2") (pintype "passive"))
      (node (ref "SW1") (pin "1") (pinfunction "1_1") (pintype "passive"))
    )
    (net (code "65") (name "Net-(R20-Pad1)") (class "Default")
      (node (ref "R20") (pin "1") (pinfunction "1_1") (pintype "passive"))
      (node (ref "S1") (pin "1") (pinfunction "1_1") (pintype "passive"))
    )
    (net (code "66") (name "Net-(R21-Pad1)") (class "Default")
      (node (ref "R21") (pin "1") (pinfunction "1_1") (pintype "passive"))
      (node (ref "S2") (pin "1") (pinfunction "1_1") (pintype "passive"))
    )
    (net (code "67") (name "Net-(R22-Pad1)") (class "Default")
      (node (ref "R22") (pin "1") (pinfunction "1_1") (pintype "passive"))
      (node (ref "S3") (pin "1") (pinfunction "1_1") (pintype "passive"))
    )
    (net (code "68") (name "Net-(R23-Pad1)") (class "Default")
      (node (ref "R23") (pin "1") (pinfunction "1_1") (pintype "passive"))
      (node (ref "S4") (pin "1") (pinfunction "1_1") (pintype "passive"))
    )
    (net (code "69") (name "Net-(R24-Pad1)") (class "Default")
      (node (ref "R24") (pin "1") (pinfunction "1_1") (pintype "passive"))
      (node (ref "S5") (pin "1") (pinfunction "1_1") (pintype "passive"))
    )
    (net (code "70") (name "Net-(R25-Pad1)") (class "Default")
      (node (ref "R25") (pin "1") (pinfunction "1_1") (pintype "passive"))
      (node (ref "S6") (pin "1") (pinfunction "1_1") (pintype "passive"))
    )
    (net (code "71") (name "Net-(R27-Pad1)") (class "Default")
      (node (ref "R27") (pin "1") (pinfunction "1_1") (pintype "passive"))
      (node (ref "S7") (pin "1") (pinfunction "1_1") (pintype "passive"))
    )
    (net (code "72") (name "Net-(R28-Pad1)") (class "Default")
      (node (ref "R28") (pin "1") (pinfunction "1_1") (pintype "passive"))
      (node (ref "S8") (pin "1") (pinfunction "1_1") (pintype "passive"))
    )
    (net (code "73") (name "Net-(R29-Pad1)") (class "Default")
      (node (ref "R29") (pin "1") (pinfunction "1_1") (pintype "passive"))
      (node (ref "S9") (pin "1") (pinfunction "1_1") (pintype "passive"))
    )
    (net (code "74") (name "Net-(R30-Pad1)") (class "Default")
      (node (ref "R30") (pin "1") (pinfunction "1_1") (pintype "passive"))
      (node (ref "S10") (pin "1") (pinfunction "1_1") (pintype "passive"))
    )
    (net (code "75") (name "Net-(R31-Pad1)") (class "Default")
      (node (ref "R31") (pin "1") (pinfunction "1_1") (pintype "passive"))
      (node (ref "S11") (pin "1") (pinfunction "1_1") (pintype "passive"))
    )
    (net (code "76") (name "Net-(R32-Pad1)") (class "Default")
      (node (ref "R32") (pin "1") (pinfunction "1_1") (pintype "passive"))
      (node (ref "S12") (pin "1") (pinfunction "1_1") (pintype "passive"))
    )
    (net (code "77") (name "Net-(R33-Pad1)") (class "Default")
      (node (ref "R33") (pin "1") (pinfunction "1_1") (pintype "passive"))
      (node (ref "S13") (pin "1") (pinfunction "1_1") (pintype "passive"))
    )
    (net (code "78") (name "Net-(R34-Pad1)") (class "Default")
      (node (ref "R34") (pin "1") (pinfunction "1_1") (pintype "passive"))
      (node (ref "S14") (pin "1") (pinfunction "1_1") (pintype "passive"))
    )
    (net (code "79") (name "Net-(R35-Pad1)") (class "Default")
      (node (ref "R35") (pin "1") (pinfunction "1_1") (pintype "passive"))
      (node (ref "S15") (pin "1") (pinfunction "1_1") (pintype "passive"))
    )
    (net (code "80") (name "Net-(R36-Pad1)") (class "Default")
      (node (ref "R36") (pin "1") (pinfunction "1_1") (pintype "passive"))
      (node (ref "S16") (pin "1") (pinfunction "1_1") (pintype "passive"))
    )
    (net (code "81") (name "Net-(R37-Pad1)") (class "Default")
      (node (ref "R37") (pin "1") (pinfunction "1_1") (pintype "passive"))
      (node (ref "S17") (pin "1") (pinfunction "1_1") (pintype "passive"))
    )
    (net (code "82") (name "Net-(R38-Pad1)") (class "Default")
      (node (ref "R38") (pin "1") (pinfunction "1_1") (pintype "passive"))
      (node (ref "S18") (pin "1") (pinfunction "1_1") (pintype "passive"))
    )
    (net (code "83") (name "Net-(R39-Pad1)") (class "Default")
      (node (ref "R39") (pin "1") (pinfunction "1_1") (pintype "passive"))
      (node (ref "S19") (pin "1") (pinfunction "1_1") (pintype "passive"))
    )
    (net (code "84") (name "Net-(R40-Pad1)") (class "Default")
      (node (ref "R40") (pin "1") (pinfunction "1_1") (pintype "passive"))
      (node (ref "S20") (pin "1") (pinfunction "1_1") (pintype "passive"))
    )
    (net (code "85") (name "Net-(R41-Pad1)") (class "Default")
      (node (ref "R41") (pin "1") (pinfunction "1_1") (pintype "passive"))
      (node (ref "S21") (pin "1") (pinfunction "1_1") (pintype "passive"))
    )
    (net (code "86") (name "Net-(R42-Pad1)") (class "Default")
      (node (ref "R42") (pin "1") (pinfunction "1_1") (pintype "passive"))
      (node (ref "S22") (pin "1") (pinfunction "1_1") (pintype "passive"))
    )
    (net (code "87") (name "Net-(R43-Pad1)") (class "Default")
      (node (ref "R43") (pin "1") (pinfunction "1_1") (pintype "passive"))
      (node (ref "S23") (pin "1") (pinfunction "1_1") (pintype "passive"))
    )
    (net (code "88") (name "Net-(R44-Pad1)") (class "Default")
      (node (ref "R44") (pin "1") (pinfunction "1_1") (pintype "passive"))
      (node (ref "S24") (pin "1") (pinfunction "1_1") (pintype "passive"))
    )
    (net (code "89") (name "Net-(U1-FB)") (class "Default")
      (node (ref "R1") (pin "1") (pinfunction "1_1") (pintype "passive"))
      (node (ref "R2") (pin "2") (pinfunction "2_2") (pintype "passive"))
      (node (ref "U1") (pin "5") (pinfunction "FB_5") (pintype "passive"))
    )
    (net (code "90") (name "Net-(U1-SW)") (class "Default")
      (node (ref "D1") (pin "2") (pinfunction "2_2") (pintype "passive"))
      (node (ref "L1") (pin "1") (pinfunction "1_1") (pintype "passive"))
      (node (ref "U1") (pin "3") (pinfunction "SW_3") (pintype "passive"))
    )
    (net (code "91") (name "Net-(U3-D+)") (class "Default")
      (node (ref "U3") (pin "3") (pinfunction "D+_3") (pintype "passive"))
      (node (ref "U4") (pin "5") (pinfunction "UD+_5") (pintype "passive"))
    )
    (net (code "92") (name "Net-(U3-D-)") (class "Default")
      (node (ref "U3") (pin "2") (pinfunction "D-_2") (pintype "passive"))
      (node (ref "U4") (pin "6") (pinfunction "UD-_6") (pintype "passive"))
    )
    (net (code "93") (name "Net-(U3-VCC)") (class "Default")
      (node (ref "D3") (pin "1") (pinfunction "1_1") (pintype "passive"))
      (node (ref "U3") (pin "1") (pinfunction "VCC_1") (pintype "passive"))
    )
    (net (code "94") (name "Net-(U8-HOLD)") (class "Default")
      (node (ref "R15") (pin "1") (pinfunction "1_1") (pintype "passive"))
      (node (ref "U8") (pin "7") (pinfunction "HOLD_7") (pintype "passive"))
    )
    (net (code "95") (name "Net-(U8-WP)") (class "Default")
      (node (ref "R14") (pin "2") (pinfunction "2_2") (pintype "passive"))
      (node (ref "U8") (pin "3") (pinfunction "WP_3") (pintype "passive"))
    )
    (net (code "96") (name "unconnected-(SW1-Pad3)") (class "Default")
      (node (ref "SW1") (pin "3") (pinfunction "3_3") (pintype "passive"))
    )
    (net (code "97") (name "unconnected-(U1-NC-Pad1)") (class "Default")
      (node (ref "U1") (pin "1") (pinfunction "NC_1") (pintype "passive"))
    )
    (net (code "98") (name "unconnected-(U1-NC-Pad6)") (class "Default")
      (node (ref "U1") (pin "6") (pinfunction "NC_6") (pintype "passive"))
    )
    (net (code "99") (name "unconnected-(U1-NC-Pad8)") (class "Default")
      (node (ref "U1") (pin "8") (pinfunction "NC_8") (pintype "passive"))
    )
    (net (code "100") (name "unconnected-(U3-ID-Pad4)") (class "Default")
      (node (ref "U3") (pin "4") (pinfunction "ID_4") (pintype "passive"))
    )
    (net (code "101") (name "unconnected-(U4-CTS#-Pad9)") (class "Default")
      (node (ref "U4") (pin "9") (pinfunction "CTS#_9") (pintype "passive+no_connect"))
    )
    (net (code "102") (name "unconnected-(U4-DCD#-Pad12)") (class "Default")
      (node (ref "U4") (pin "12") (pinfunction "DCD#_12") (pintype "passive+no_connect"))
    )
    (net (code "103") (name "unconnected-(U4-DSR#-Pad10)") (class "Default")
      (node (ref "U4") (pin "10") (pinfunction "DSR#_10") (pintype "passive+no_connect"))
    )
    (net (code "104") (name "unconnected-(U4-DTR#-Pad13)") (class "Default")
      (node (ref "U4") (pin "13") (pinfunction "DTR#_13") (pintype "passive+no_connect"))
    )
    (net (code "105") (name "unconnected-(U4-R232-Pad15)") (class "Default")
      (node (ref "U4") (pin "15") (pinfunction "R232_15") (pintype "passive+no_connect"))
    )
    (net (code "106") (name "unconnected-(U4-RI#-Pad11)") (class "Default")
      (node (ref "U4") (pin "11") (pinfunction "RI#_11") (pintype "passive+no_connect"))
    )
    (net (code "107") (name "unconnected-(U4-RTS#-Pad14)") (class "Default")
      (node (ref "U4") (pin "14") (pinfunction "RTS#_14") (pintype "passive+no_connect"))
    )
    (net (code "108") (name "unconnected-(U4-XI-Pad7)") (class "Default")
      (node (ref "U4") (pin "7") (pinfunction "XI_7") (pintype "passive+no_connect"))
    )
    (net (code "109") (name "unconnected-(U4-XO-Pad8)") (class "Default")
      (node (ref "U4") (pin "8") (pinfunction "XO_8") (pintype "passive+no_connect"))
    )
    (net (code "110") (name "unconnected-(U5-PC14-OSC32_IN-Pad3)") (class "Default")
      (node (ref "U5") (pin "3") (pinfunction "PC14-OSC32_IN_3") (pintype "passive"))
    )
    (net (code "111") (name "unconnected-(U5-PC15-OSC32_OUT-Pad4)") (class "Default")
      (node (ref "U5") (pin "4") (pinfunction "PC15-OSC32_OUT_4") (pintype "passive"))
    )
    (net (code "112") (name "unconnected-(X1-NO-Pad4)") (class "Default")
      (node (ref "X1") (pin "4") (pinfunction "NO_4") (pintype "passive"))
    )
  )
)
